# EasyEDA_Schematic_-_Bipolar_Stepper_Moto.net
KiCad netlist of a schematic drawn in EasyEDA
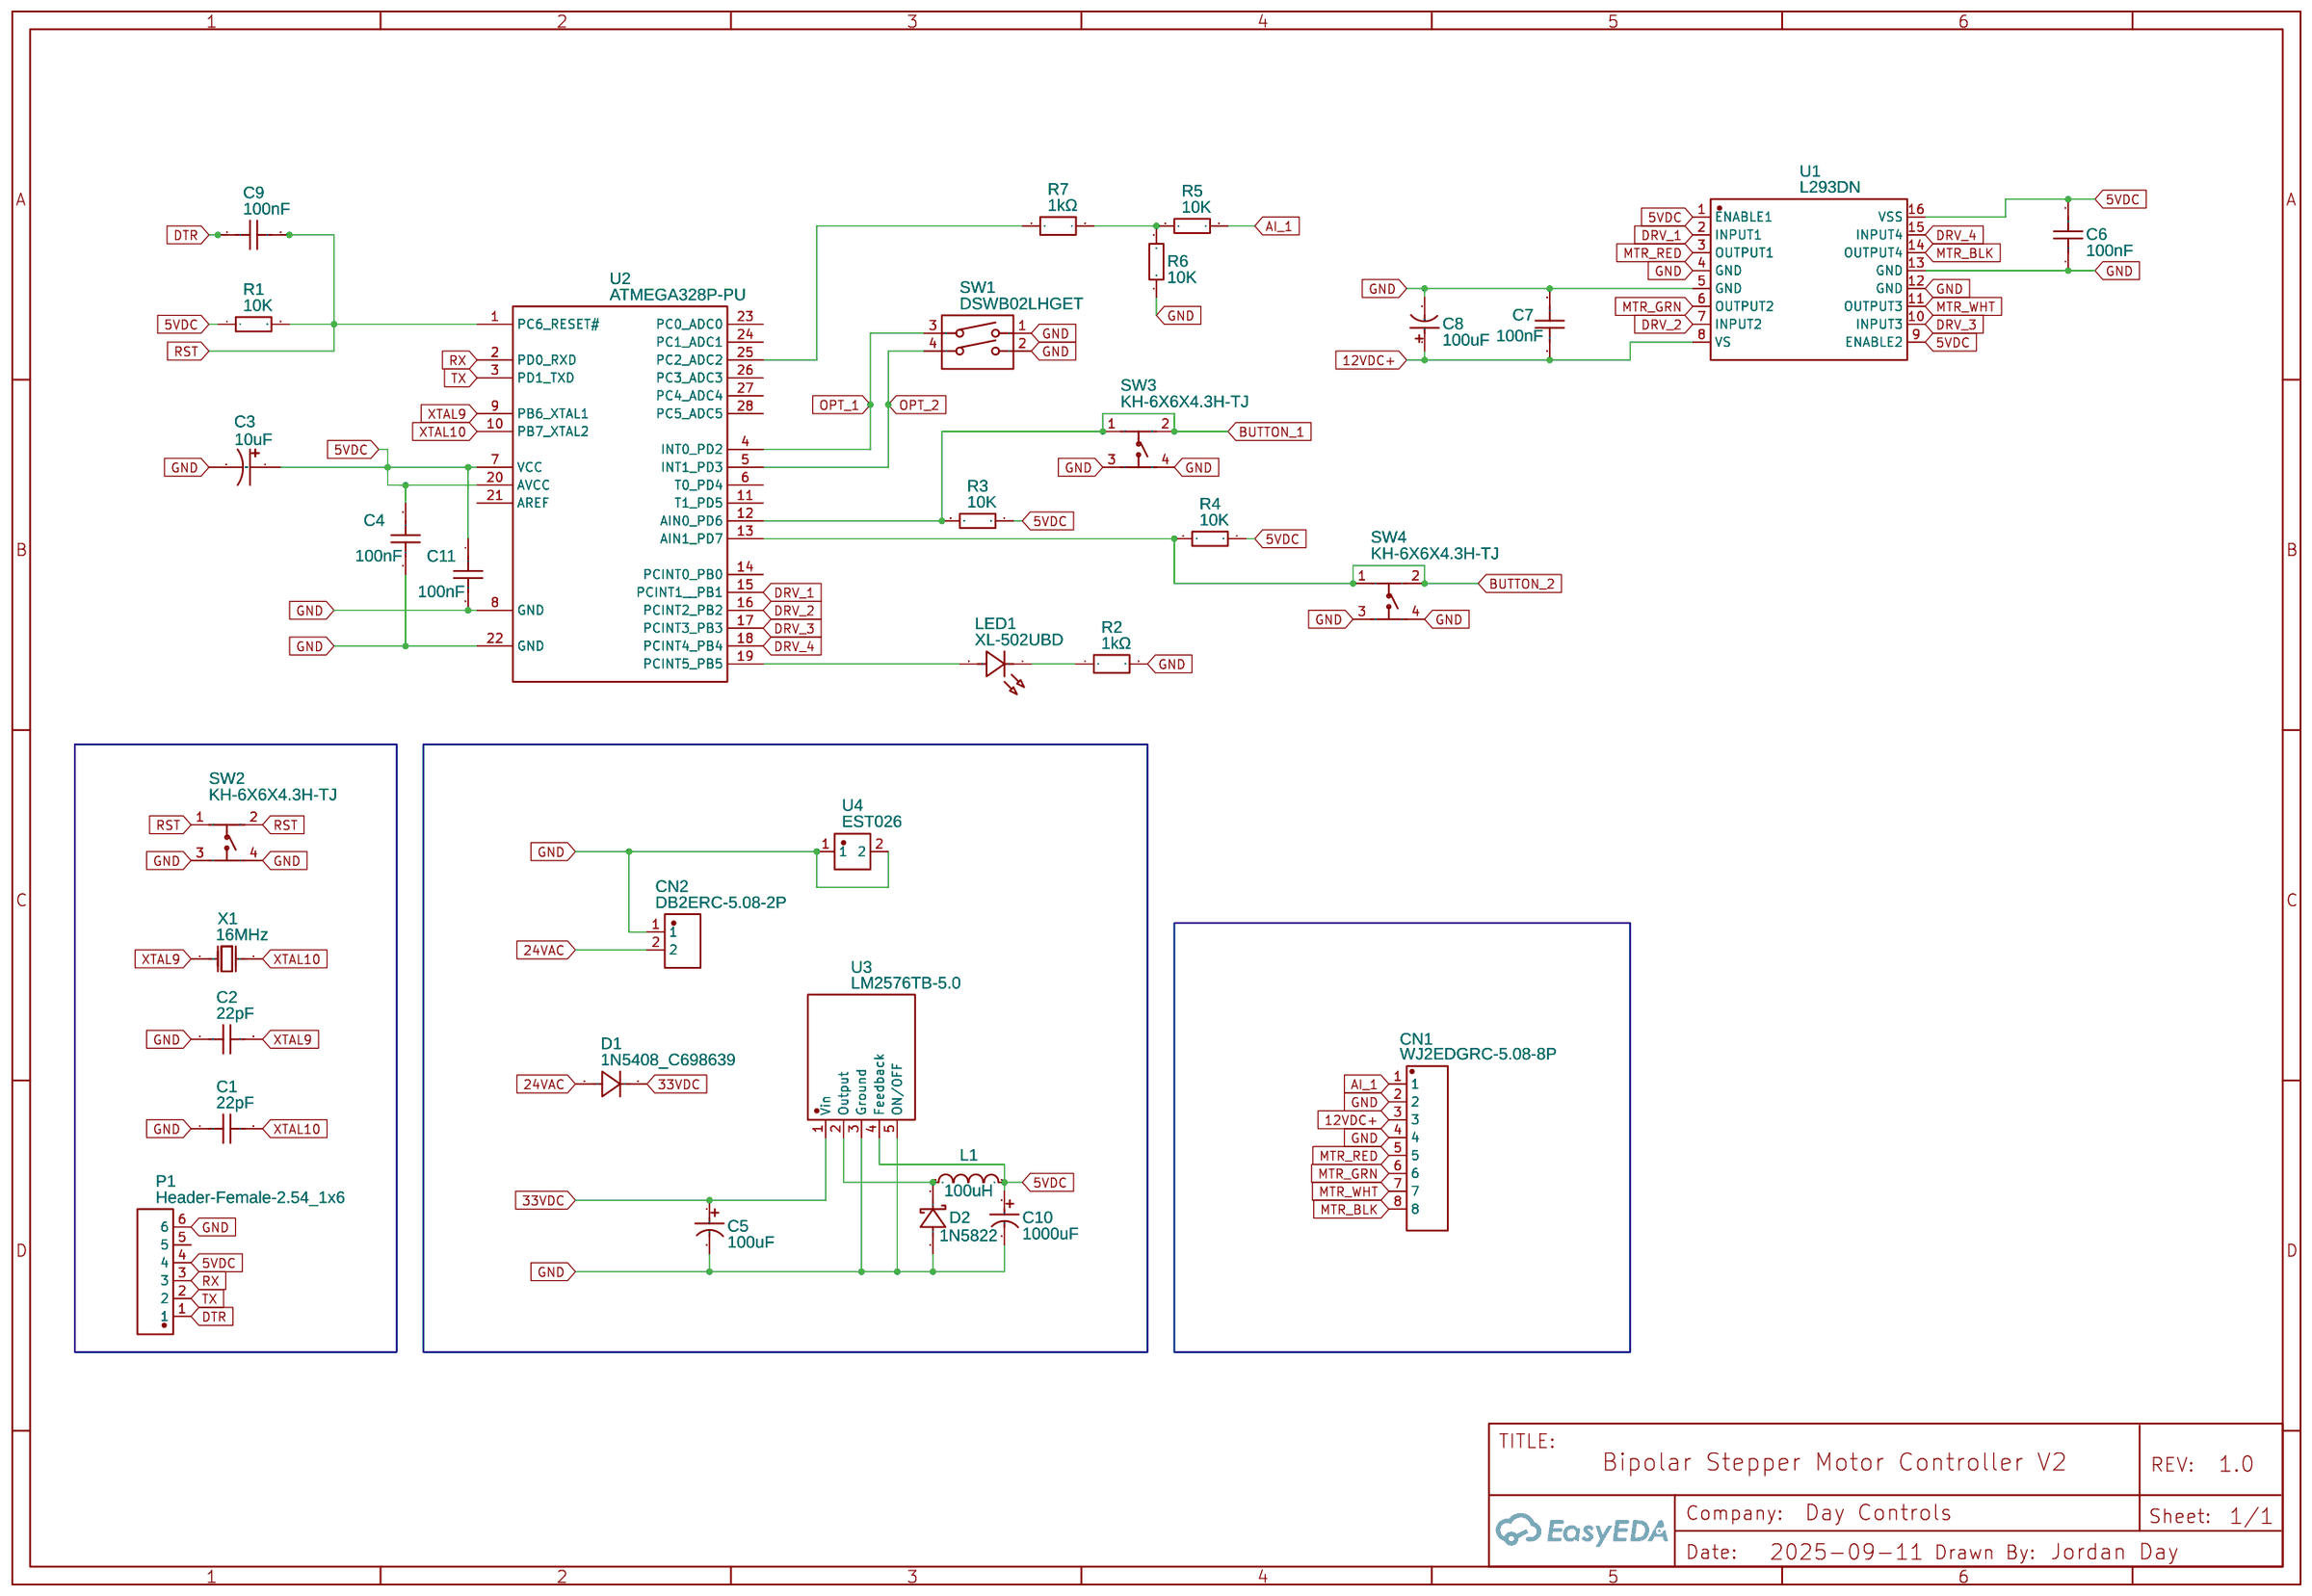
[diagram p0: schematic sheet]

(export (version "E")
  (design (tool "Eeschema 10.0.6"))
  (components
    (comp (ref "C1")
      (value "22pF")
      (fields
        (field (name "Manufacturer Part") "DCH220K22YR N6FH5GD")
        (field (name "Manufacturer") "SHM(南方宏明)")
      )
      (libsource (lib "") (part "DCH220K22YR N6FH5GD"))
    )
    (comp (ref "C2")
      (value "22pF")
      (fields
        (field (name "Manufacturer Part") "DCH220K22YR N6FH5GD")
        (field (name "Manufacturer") "SHM(南方宏明)")
      )
      (libsource (lib "") (part "DCH220K22YR N6FH5GD"))
    )
    (comp (ref "C3")
      (value "10uF")
      (fields
        (field (name "Manufacturer Part") "ECR1HPT100MLL050011")
        (field (name "Manufacturer") "Nantong Jianghai Capacitor")
      )
      (libsource (lib "") (part "ECR1HPT100MLL050011"))
    )
    (comp (ref "C4")
      (value "100nF")
      (fields
        (field (name "Manufacturer Part") "CC1H104MC1FD3F6C10MF")
        (field (name "Manufacturer") "Dersonic(德尔创)")
      )
      (libsource (lib "") (part "CC1H104MC1FD3F6C10MF_1"))
    )
    (comp (ref "C5")
      (value "100uF")
      (fields
        (field (name "Manufacturer Part") "GR107M050F12RR0VH4FP0")
        (field (name "Manufacturer") "CX(承兴)")
      )
      (libsource (lib "") (part "100uF 50V 8*12Black high frequency_1"))
    )
    (comp (ref "C6")
      (value "100nF")
      (fields
        (field (name "Manufacturer Part") "CC1H104MC1FD3F6C10MF")
        (field (name "Manufacturer") "Dersonic(德尔创)")
      )
      (libsource (lib "") (part "CC1H104MC1FD3F6C10MF"))
    )
    (comp (ref "C7")
      (value "100nF")
      (fields
        (field (name "Manufacturer Part") "CC1H104MC1FD3F6C10MF")
        (field (name "Manufacturer") "Dersonic(德尔创)")
      )
      (libsource (lib "") (part "CC1H104MC1FD3F6C10MF"))
    )
    (comp (ref "C8")
      (value "100uF")
      (fields
        (field (name "Manufacturer Part") "GR107M050F12RR0VH4FP0")
        (field (name "Manufacturer") "CX(承兴)")
      )
      (libsource (lib "") (part "100uF 50V 8*12Black high frequency"))
    )
    (comp (ref "C9")
      (value "100nF")
      (fields
        (field (name "Manufacturer Part") "CC1H104MC1FD3F6C10MF")
        (field (name "Manufacturer") "Dersonic(德尔创)")
      )
      (libsource (lib "") (part "CC1H104MC1FD3F6C10MF_2"))
    )
    (comp (ref "C10")
      (value "1000uF")
      (fields
        (field (name "Manufacturer Part") "35YXJ1000M12.5X20")
        (field (name "Manufacturer") "rubycon(红宝石)")
      )
      (libsource (lib "") (part "35YXJ1000M12.5X20"))
    )
    (comp (ref "C11")
      (value "100nF")
      (fields
        (field (name "Manufacturer Part") "CC1H104MC1FD3F6C10MF")
        (field (name "Manufacturer") "Dersonic(德尔创)")
      )
      (libsource (lib "") (part "CC1H104MC1FD3F6C10MF_1"))
    )
    (comp (ref "CN1")
      (value "WJ2EDGRC-5.08-8P")
      (fields (field (name "Manufacturer") "KANGNEX(康奈克斯电气)"))
      (libsource (lib "") (part "WJ2EDGRC-5.08-8P"))
    )
    (comp (ref "CN2")
      (value "DB2ERC-5.08-2P")
      (fields
        (field (name "Manufacturer Part") "DB2ERC-5.08-2P-GN")
        (field (name "Manufacturer") "DIBO(地博电气)")
      )
      (libsource (lib "") (part "DB2ERC-5.08-2P"))
    )
    (comp (ref "D1")
      (value "1N5408_C698639")
      (fields (field (name "Manufacturer Part") "1N5408") (field (name "Manufacturer") "YANGJIE(扬杰)"))
      (libsource (lib "") (part "1N5408_C698639"))
    )
    (comp (ref "D2")
      (value "1N5822")
      (fields (field (name "Manufacturer") "FUXINSEMI(富芯森美)"))
      (libsource (lib "") (part "1N5822_C3018526"))
    )
    (comp (ref "L1")
      (value "100uH")
      (fields (field (name "Manufacturer Part") "VLU0810-101K") (field (name "Manufacturer") "FH(风华)"))
      (libsource (lib "") (part "VLU0810-101K"))
    )
    (comp (ref "LED1")
      (value "XL-502UBD")
      (fields (field (name "Manufacturer") "XINGLIGHT(成兴光)"))
      (libsource (lib "") (part "XL-502UBD"))
    )
    (comp (ref "P1")
      (value "Header-Female-2.54_1x6")
      (fields (field (name "Manufacturer Part") "2.54-1*6P母") (field (name "Manufacturer") "BOOMELE(博穆精密)"))
      (libsource (lib "") (part "Header-Female-2.54_1x6"))
    )
    (comp (ref "R1")
      (value "10K")
      (fields (field (name "Manufacturer Part") "MFR50SFTE52-10K") (field (name "Manufacturer") "YAGEO(国巨)"))
      (libsource (lib "") (part "MFR50SFTE52-10K_2"))
    )
    (comp (ref "R2")
      (value "1kΩ")
      (fields
        (field (name "Manufacturer Part") "MF1/4W-1KΩ±1%T52")
        (field (name "Manufacturer") "Huaxing Mechanical-Elec.")
      )
      (libsource (lib "") (part "MF1/4W-1KΩ±1%T52"))
    )
    (comp (ref "R3")
      (value "10K")
      (fields (field (name "Manufacturer Part") "MFR50SFTE52-10K") (field (name "Manufacturer") "YAGEO(国巨)"))
      (libsource (lib "") (part "MFR50SFTE52-10K"))
    )
    (comp (ref "R4")
      (value "10K")
      (fields (field (name "Manufacturer Part") "MFR50SFTE52-10K") (field (name "Manufacturer") "YAGEO(国巨)"))
      (libsource (lib "") (part "MFR50SFTE52-10K"))
    )
    (comp (ref "R5")
      (value "10K")
      (fields (field (name "Manufacturer Part") "MFR50SFTE52-10K") (field (name "Manufacturer") "YAGEO(国巨)"))
      (libsource (lib "") (part "MFR50SFTE52-10K"))
    )
    (comp (ref "R6")
      (value "10K")
      (fields (field (name "Manufacturer Part") "MFR50SFTE52-10K") (field (name "Manufacturer") "YAGEO(国巨)"))
      (libsource (lib "") (part "MFR50SFTE52-10K_1"))
    )
    (comp (ref "R7")
      (value "1kΩ")
      (fields
        (field (name "Manufacturer Part") "MF1/4W-1KΩ±1%T52")
        (field (name "Manufacturer") "Huaxing Mechanical-Elec.")
      )
      (libsource (lib "") (part "MF1/4W-1KΩ±1%T52"))
    )
    (comp (ref "SW1")
      (value "DSWB02LHGET")
      (fields (field (name "Manufacturer") "YE"))
      (libsource (lib "") (part "DSWB02LHGET"))
    )
    (comp (ref "SW2")
      (value "KH-6X6X4.3H-TJ")
      (fields (field (name "Manufacturer") "kinghelm(金航标)"))
      (libsource (lib "") (part "KH-6X6X4.3H-TJ"))
    )
    (comp (ref "SW3")
      (value "KH-6X6X4.3H-TJ")
      (fields (field (name "Manufacturer") "kinghelm(金航标)"))
      (libsource (lib "") (part "KH-6X6X4.3H-TJ"))
    )
    (comp (ref "SW4")
      (value "KH-6X6X4.3H-TJ")
      (fields (field (name "Manufacturer") "kinghelm(金航标)"))
      (libsource (lib "") (part "KH-6X6X4.3H-TJ"))
    )
    (comp (ref "U1")
      (value "L293DN")
      (fields (field (name "Manufacturer") "HGSEMI(华冠)"))
      (libsource (lib "") (part "L293DN"))
    )
    (comp (ref "U2")
      (value "ATMEGA328P-PU")
      (fields (field (name "Manufacturer") "MICROCHIP(美国微芯)"))
      (libsource (lib "") (part "ATMEGA328P-PU"))
    )
    (comp (ref "U3")
      (value "LM2576TB-5.0")
      (fields (field (name "Manufacturer") "HGSEMI(华冠)"))
      (libsource (lib "") (part "LM2576TB-5.0"))
    )
    (comp (ref "U4")
      (value "EST026")
      (fields (field (name "Manufacturer") "xcfuse(旭程)"))
      (libsource (lib "") (part "EST026"))
    )
    (comp (ref "X1")
      (value "16MHz")
      (fields (field (name "Manufacturer Part") "X49SD16MSD2SC") (field (name "Manufacturer") "YXC(扬兴晶振)"))
      (libsource (lib "") (part "X49SD16MSD2SC"))
    )
  )
  (nets
    (net (code "1") (name "5VDC") (class "Default")
      (node (ref "C10") (pin "1") (pinfunction "1_1") (pintype "input"))
      (node (ref "C11") (pin "1") (pinfunction "1_1") (pintype "unspecified"))
      (node (ref "C3") (pin "1") (pinfunction "1_1") (pintype "unspecified"))
      (node (ref "C4") (pin "1") (pinfunction "1_1") (pintype "unspecified"))
      (node (ref "C6") (pin "2") (pinfunction "2_2") (pintype "unspecified"))
      (node (ref "L1") (pin "2") (pinfunction "2_2") (pintype "unspecified"))
      (node (ref "P1") (pin "4") (pinfunction "4_4") (pintype "unspecified"))
      (node (ref "R1") (pin "1") (pinfunction "1_1") (pintype "unspecified"))
      (node (ref "R3") (pin "1") (pinfunction "1_1") (pintype "unspecified"))
      (node (ref "R4") (pin "1") (pinfunction "1_1") (pintype "unspecified"))
      (node (ref "U1") (pin "1") (pinfunction "ENABLE1_1") (pintype "unspecified"))
      (node (ref "U1") (pin "16") (pinfunction "VSS_16") (pintype "unspecified"))
      (node (ref "U1") (pin "9") (pinfunction "ENABLE2_9") (pintype "unspecified"))
      (node (ref "U2") (pin "20") (pinfunction "AVCC_20") (pintype "passive"))
      (node (ref "U2") (pin "7") (pinfunction "VCC_7") (pintype "passive"))
      (node (ref "U3") (pin "4") (pinfunction "Feedback_4") (pintype "unspecified"))
    )
    (net (code "2") (name "12VDC+") (class "Default")
      (node (ref "C7") (pin "1") (pinfunction "1_1") (pintype "unspecified"))
      (node (ref "C8") (pin "1") (pinfunction "1_1") (pintype "input"))
      (node (ref "CN1") (pin "3") (pinfunction "3_3") (pintype "unspecified"))
      (node (ref "U1") (pin "8") (pinfunction "VS_8") (pintype "unspecified"))
    )
    (net (code "3") (name "24VAC") (class "Default")
      (node (ref "CN2") (pin "2") (pinfunction "2_2") (pintype "unspecified"))
      (node (ref "D1") (pin "2") (pinfunction "A_2") (pintype "unspecified"))
    )
    (net (code "4") (name "33VDC") (class "Default")
      (node (ref "C5") (pin "1") (pinfunction "1_1") (pintype "input"))
      (node (ref "D1") (pin "1") (pinfunction "K_1") (pintype "unspecified"))
      (node (ref "U3") (pin "1") (pinfunction "Vin_1") (pintype "unspecified"))
    )
    (net (code "5") (name "AI_1") (class "Default")
      (node (ref "CN1") (pin "1") (pinfunction "1_1") (pintype "unspecified"))
      (node (ref "R5") (pin "1") (pinfunction "1_1") (pintype "unspecified"))
    )
    (net (code "6") (name "BUTTON_1") (class "Default")
      (node (ref "R3") (pin "2") (pinfunction "2_2") (pintype "unspecified"))
      (node (ref "SW3") (pin "1") (pinfunction "1_1") (pintype "unspecified"))
      (node (ref "SW3") (pin "2") (pinfunction "2_2") (pintype "unspecified"))
      (node (ref "U2") (pin "12") (pinfunction "AIN0_PD6_12") (pintype "bidirectional"))
    )
    (net (code "7") (name "BUTTON_2") (class "Default")
      (node (ref "R4") (pin "2") (pinfunction "2_2") (pintype "unspecified"))
      (node (ref "SW4") (pin "1") (pinfunction "1_1") (pintype "unspecified"))
      (node (ref "SW4") (pin "2") (pinfunction "2_2") (pintype "unspecified"))
      (node (ref "U2") (pin "13") (pinfunction "AIN1_PD7_13") (pintype "bidirectional"))
    )
    (net (code "8") (name "DRV_1") (class "Default")
      (node (ref "U1") (pin "2") (pinfunction "INPUT1_2") (pintype "unspecified"))
      (node (ref "U2") (pin "15") (pinfunction "PCINT1__PB1_15") (pintype "bidirectional"))
    )
    (net (code "9") (name "DRV_2") (class "Default")
      (node (ref "U1") (pin "7") (pinfunction "INPUT2_7") (pintype "unspecified"))
      (node (ref "U2") (pin "16") (pinfunction "PCINT2_PB2_16") (pintype "bidirectional"))
    )
    (net (code "10") (name "DRV_3") (class "Default")
      (node (ref "U1") (pin "10") (pinfunction "INPUT3_10") (pintype "unspecified"))
      (node (ref "U2") (pin "17") (pinfunction "PCINT3_PB3_17") (pintype "bidirectional"))
    )
    (net (code "11") (name "DRV_4") (class "Default")
      (node (ref "U1") (pin "15") (pinfunction "INPUT4_15") (pintype "unspecified"))
      (node (ref "U2") (pin "18") (pinfunction "PCINT4_PB4_18") (pintype "bidirectional"))
    )
    (net (code "12") (name "DTR") (class "Default")
      (node (ref "C9") (pin "1") (pinfunction "1_1") (pintype "unspecified"))
      (node (ref "P1") (pin "1") (pinfunction "1_1") (pintype "unspecified"))
    )
    (net (code "13") (name "GND") (class "Default")
      (node (ref "C1") (pin "1") (pinfunction "1_1") (pintype "unspecified"))
      (node (ref "C10") (pin "2") (pinfunction "2_2") (pintype "input"))
      (node (ref "C11") (pin "2") (pinfunction "2_2") (pintype "unspecified"))
      (node (ref "C2") (pin "1") (pinfunction "1_1") (pintype "unspecified"))
      (node (ref "C3") (pin "2") (pinfunction "2_2") (pintype "unspecified"))
      (node (ref "C4") (pin "2") (pinfunction "2_2") (pintype "unspecified"))
      (node (ref "C5") (pin "2") (pinfunction "2_2") (pintype "input"))
      (node (ref "C6") (pin "1") (pinfunction "1_1") (pintype "unspecified"))
      (node (ref "C7") (pin "2") (pinfunction "2_2") (pintype "unspecified"))
      (node (ref "C8") (pin "2") (pinfunction "2_2") (pintype "input"))
      (node (ref "CN1") (pin "2") (pinfunction "2_2") (pintype "unspecified"))
      (node (ref "CN1") (pin "4") (pinfunction "4_4") (pintype "unspecified"))
      (node (ref "CN2") (pin "1") (pinfunction "1_1") (pintype "unspecified"))
      (node (ref "D2") (pin "1") (pinfunction "A_1") (pintype "unspecified"))
      (node (ref "P1") (pin "6") (pinfunction "6_6") (pintype "unspecified"))
      (node (ref "R2") (pin "2") (pinfunction "2_2") (pintype "unspecified"))
      (node (ref "R6") (pin "2") (pinfunction "2_2") (pintype "unspecified"))
      (node (ref "SW1") (pin "1") (pinfunction "1_1") (pintype "unspecified"))
      (node (ref "SW1") (pin "2") (pinfunction "2_2") (pintype "unspecified"))
      (node (ref "SW2") (pin "3") (pinfunction "3_3") (pintype "unspecified"))
      (node (ref "SW2") (pin "4") (pinfunction "4_4") (pintype "unspecified"))
      (node (ref "SW3") (pin "3") (pinfunction "3_3") (pintype "unspecified"))
      (node (ref "SW3") (pin "4") (pinfunction "4_4") (pintype "unspecified"))
      (node (ref "SW4") (pin "3") (pinfunction "3_3") (pintype "unspecified"))
      (node (ref "SW4") (pin "4") (pinfunction "4_4") (pintype "unspecified"))
      (node (ref "U1") (pin "12") (pinfunction "GND_12") (pintype "unspecified"))
      (node (ref "U1") (pin "13") (pinfunction "GND_13") (pintype "unspecified"))
      (node (ref "U1") (pin "4") (pinfunction "GND_4") (pintype "unspecified"))
      (node (ref "U1") (pin "5") (pinfunction "GND_5") (pintype "unspecified"))
      (node (ref "U2") (pin "22") (pinfunction "GND_22") (pintype "passive"))
      (node (ref "U2") (pin "8") (pinfunction "GND_8") (pintype "passive"))
      (node (ref "U3") (pin "3") (pinfunction "Ground_3") (pintype "unspecified"))
      (node (ref "U3") (pin "5") (pinfunction "ON/OFF_5") (pintype "unspecified"))
      (node (ref "U4") (pin "1") (pinfunction "1_1") (pintype "unspecified"))
      (node (ref "U4") (pin "2") (pinfunction "2_2") (pintype "unspecified"))
    )
    (net (code "14") (name "MTR_BLK") (class "Default")
      (node (ref "CN1") (pin "8") (pinfunction "8_8") (pintype "unspecified"))
      (node (ref "U1") (pin "14") (pinfunction "OUTPUT4_14") (pintype "unspecified"))
    )
    (net (code "15") (name "MTR_GRN") (class "Default")
      (node (ref "CN1") (pin "6") (pinfunction "6_6") (pintype "unspecified"))
      (node (ref "U1") (pin "6") (pinfunction "OUTPUT2_6") (pintype "unspecified"))
    )
    (net (code "16") (name "MTR_RED") (class "Default")
      (node (ref "CN1") (pin "5") (pinfunction "5_5") (pintype "unspecified"))
      (node (ref "U1") (pin "3") (pinfunction "OUTPUT1_3") (pintype "unspecified"))
    )
    (net (code "17") (name "MTR_WHT") (class "Default")
      (node (ref "CN1") (pin "7") (pinfunction "7_7") (pintype "unspecified"))
      (node (ref "U1") (pin "11") (pinfunction "OUTPUT3_11") (pintype "unspecified"))
    )
    (net (code "18") (name "Net-(D2-K)") (class "Default")
      (node (ref "D2") (pin "2") (pinfunction "K_2") (pintype "unspecified"))
      (node (ref "L1") (pin "1") (pinfunction "1_1") (pintype "unspecified"))
      (node (ref "U3") (pin "2") (pinfunction "Output_2") (pintype "unspecified"))
    )
    (net (code "19") (name "Net-(LED1-A)") (class "Default")
      (node (ref "LED1") (pin "2") (pinfunction "A_2") (pintype "unspecified"))
      (node (ref "U2") (pin "19") (pinfunction "PCINT5_PB5_19") (pintype "bidirectional"))
    )
    (net (code "20") (name "Net-(LED1-K)") (class "Default")
      (node (ref "LED1") (pin "1") (pinfunction "K_1") (pintype "unspecified"))
      (node (ref "R2") (pin "1") (pinfunction "1_1") (pintype "unspecified"))
    )
    (net (code "21") (name "Net-(R5-Pad2)") (class "Default")
      (node (ref "R5") (pin "2") (pinfunction "2_2") (pintype "unspecified"))
      (node (ref "R6") (pin "1") (pinfunction "1_1") (pintype "unspecified"))
      (node (ref "R7") (pin "2") (pinfunction "2_2") (pintype "unspecified"))
    )
    (net (code "22") (name "Net-(U2-PC2_ADC2)") (class "Default")
      (node (ref "R7") (pin "1") (pinfunction "1_1") (pintype "unspecified"))
      (node (ref "U2") (pin "25") (pinfunction "PC2_ADC2_25") (pintype "bidirectional"))
    )
    (net (code "23") (name "OPT_1") (class "Default")
      (node (ref "SW1") (pin "3") (pinfunction "3_3") (pintype "unspecified"))
      (node (ref "U2") (pin "4") (pinfunction "INT0_PD2_4") (pintype "bidirectional"))
    )
    (net (code "24") (name "OPT_2") (class "Default")
      (node (ref "SW1") (pin "4") (pinfunction "4_4") (pintype "unspecified"))
      (node (ref "U2") (pin "5") (pinfunction "INT1_PD3_5") (pintype "bidirectional"))
    )
    (net (code "25") (name "RST") (class "Default")
      (node (ref "C9") (pin "2") (pinfunction "2_2") (pintype "unspecified"))
      (node (ref "R1") (pin "2") (pinfunction "2_2") (pintype "unspecified"))
      (node (ref "SW2") (pin "1") (pinfunction "1_1") (pintype "unspecified"))
      (node (ref "SW2") (pin "2") (pinfunction "2_2") (pintype "unspecified"))
      (node (ref "U2") (pin "1") (pinfunction "PC6_RESET#_1") (pintype "bidirectional"))
    )
    (net (code "26") (name "RX") (class "Default")
      (node (ref "P1") (pin "3") (pinfunction "3_3") (pintype "unspecified"))
      (node (ref "U2") (pin "2") (pinfunction "PD0_RXD_2") (pintype "bidirectional"))
    )
    (net (code "27") (name "TX") (class "Default")
      (node (ref "P1") (pin "2") (pinfunction "2_2") (pintype "unspecified"))
      (node (ref "U2") (pin "3") (pinfunction "PD1_TXD_3") (pintype "bidirectional"))
    )
    (net (code "28") (name "XTAL9") (class "Default")
      (node (ref "C2") (pin "2") (pinfunction "2_2") (pintype "unspecified"))
      (node (ref "U2") (pin "9") (pinfunction "PB6_XTAL1_9") (pintype "bidirectional"))
      (node (ref "X1") (pin "2") (pinfunction "OSC2_2") (pintype "input"))
    )
    (net (code "29") (name "XTAL10") (class "Default")
      (node (ref "C1") (pin "2") (pinfunction "2_2") (pintype "unspecified"))
      (node (ref "U2") (pin "10") (pinfunction "PB7_XTAL2_10") (pintype "bidirectional"))
      (node (ref "X1") (pin "1") (pinfunction "OSC1_1") (pintype "input"))
    )
    (net (code "30") (name "unconnected-(P1-Pad5)") (class "Default")
      (node (ref "P1") (pin "5") (pinfunction "5_5") (pintype "unspecified"))
    )
    (net (code "31") (name "unconnected-(U2-AREF-Pad21)") (class "Default")
      (node (ref "U2") (pin "21") (pinfunction "AREF_21") (pintype "passive"))
    )
    (net (code "32") (name "unconnected-(U2-PC0_ADC0-Pad23)") (class "Default")
      (node (ref "U2") (pin "23") (pinfunction "PC0_ADC0_23") (pintype "bidirectional"))
    )
    (net (code "33") (name "unconnected-(U2-PC1_ADC1-Pad24)") (class "Default")
      (node (ref "U2") (pin "24") (pinfunction "PC1_ADC1_24") (pintype "bidirectional"))
    )
    (net (code "34") (name "unconnected-(U2-PC3_ADC3-Pad26)") (class "Default")
      (node (ref "U2") (pin "26") (pinfunction "PC3_ADC3_26") (pintype "bidirectional"))
    )
    (net (code "35") (name "unconnected-(U2-PC4_ADC4-Pad27)") (class "Default")
      (node (ref "U2") (pin "27") (pinfunction "PC4_ADC4_27") (pintype "bidirectional"))
    )
    (net (code "36") (name "unconnected-(U2-PC5_ADC5-Pad28)") (class "Default")
      (node (ref "U2") (pin "28") (pinfunction "PC5_ADC5_28") (pintype "bidirectional"))
    )
    (net (code "37") (name "unconnected-(U2-PCINT0_PB0-Pad14)") (class "Default")
      (node (ref "U2") (pin "14") (pinfunction "PCINT0_PB0_14") (pintype "bidirectional"))
    )
    (net (code "38") (name "unconnected-(U2-T0_PD4-Pad6)") (class "Default")
      (node (ref "U2") (pin "6") (pinfunction "T0_PD4_6") (pintype "bidirectional"))
    )
    (net (code "39") (name "unconnected-(U2-T1_PD5-Pad11)") (class "Default")
      (node (ref "U2") (pin "11") (pinfunction "T1_PD5_11") (pintype "bidirectional"))
    )
  )
)
